# MoonlightHub.net
KiCad netlist of a schematic drawn in EAGLE
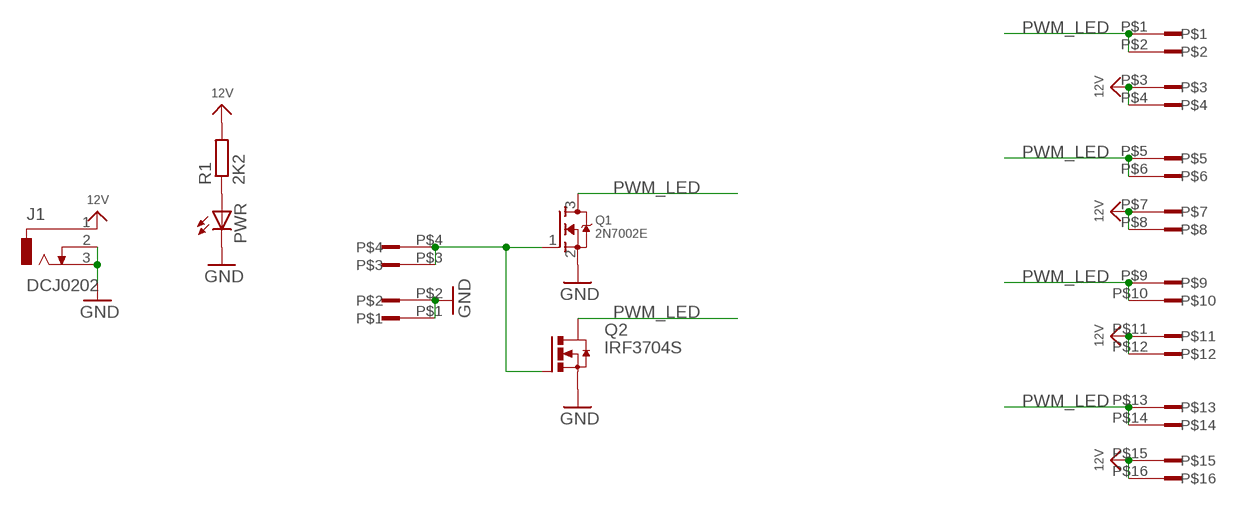
[diagram p0: schematic, sheet 1]

(export (version "E")
  (design (tool "Eeschema 10.0.6"))
  (components
    (comp (ref "CON1")
      (value "CONN2")
      (footprint "eagle-import:CONN2")
      (libsource (lib "eagle-import") (part "CONN2"))
    )
    (comp (ref "CON2")
      (value "CONN8")
      (footprint "eagle-import:CONN8")
      (libsource (lib "eagle-import") (part "CONN8"))
    )
    (comp (ref "J1")
      (value "DCJ0202")
      (footprint "eagle-import:DCJ0202")
      (libsource (lib "eagle-import") (part "DCJ0202"))
    )
    (comp (ref "PWR")
      (value "LED3MM")
      (footprint "eagle-import:LED3MM")
      (libsource (lib "eagle-import") (part "LED3MM"))
    )
    (comp (ref "Q1")
      (value "2N7002E")
      (footprint "eagle-import:SOT23-W")
      (libsource (lib "eagle-import") (part "MOSFET-NWAVE"))
    )
    (comp (ref "Q2")
      (value "IRF3704S")
      (footprint "eagle-import:D2PACK")
      (libsource (lib "eagle-import") (part "IRF3704S"))
    )
    (comp (ref "R1")
      (value "2K2")
      (footprint "eagle-import:R0805W")
      (libsource (lib "eagle-import") (part "R-EU_R0805W"))
    )
  )
  (nets
    (net (code "1") (name "/PWM_LED") (class "Default")
      (node (ref "CON2") (pin "P$1") (pinfunction "P$1_P$1") (pintype "bidirectional"))
      (node (ref "CON2") (pin "P$10") (pinfunction "P$10_P$10") (pintype "bidirectional"))
      (node (ref "CON2") (pin "P$13") (pinfunction "P$13_P$13") (pintype "bidirectional"))
      (node (ref "CON2") (pin "P$14") (pinfunction "P$14_P$14") (pintype "bidirectional"))
      (node (ref "CON2") (pin "P$2") (pinfunction "P$2_P$2") (pintype "bidirectional"))
      (node (ref "CON2") (pin "P$5") (pinfunction "P$5_P$5") (pintype "bidirectional"))
      (node (ref "CON2") (pin "P$6") (pinfunction "P$6_P$6") (pintype "bidirectional"))
      (node (ref "CON2") (pin "P$9") (pinfunction "P$9_P$9") (pintype "bidirectional"))
      (node (ref "Q1") (pin "3") (pinfunction "D_3") (pintype "bidirectional"))
      (node (ref "Q2") (pin "2") (pinfunction "D_2") (pintype "passive"))
    )
    (net (code "2") (name "12V") (class "Default")
      (node (ref "CON2") (pin "P$11") (pinfunction "P$11_P$11") (pintype "bidirectional"))
      (node (ref "CON2") (pin "P$12") (pinfunction "P$12_P$12") (pintype "bidirectional"))
      (node (ref "CON2") (pin "P$15") (pinfunction "P$15_P$15") (pintype "bidirectional"))
      (node (ref "CON2") (pin "P$16") (pinfunction "P$16_P$16") (pintype "bidirectional"))
      (node (ref "CON2") (pin "P$3") (pinfunction "P$3_P$3") (pintype "bidirectional"))
      (node (ref "CON2") (pin "P$4") (pinfunction "P$4_P$4") (pintype "bidirectional"))
      (node (ref "CON2") (pin "P$7") (pinfunction "P$7_P$7") (pintype "bidirectional"))
      (node (ref "CON2") (pin "P$8") (pinfunction "P$8_P$8") (pintype "bidirectional"))
      (node (ref "J1") (pin "1") (pinfunction "1_1") (pintype "passive"))
      (node (ref "R1") (pin "2") (pinfunction "2_2") (pintype "passive"))
    )
    (net (code "3") (name "GND") (class "Default")
      (node (ref "CON1") (pin "P$1") (pinfunction "P$1_P$1") (pintype "bidirectional"))
      (node (ref "CON1") (pin "P$2") (pinfunction "P$2_P$2") (pintype "bidirectional"))
      (node (ref "J1") (pin "2") (pinfunction "2_2") (pintype "passive"))
      (node (ref "J1") (pin "3") (pinfunction "3_3") (pintype "passive"))
      (node (ref "PWR") (pin "K") (pinfunction "C_K") (pintype "passive"))
      (node (ref "Q1") (pin "2") (pinfunction "S_2") (pintype "bidirectional"))
      (node (ref "Q2") (pin "3") (pinfunction "S_3") (pintype "passive"))
    )
    (net (code "4") (name "Net-(PWR-PadA)") (class "Default")
      (node (ref "PWR") (pin "A") (pinfunction "A_A") (pintype "passive"))
      (node (ref "R1") (pin "1") (pinfunction "1_1") (pintype "passive"))
    )
    (net (code "5") (name "Net-(Q1-G)") (class "Default")
      (node (ref "CON1") (pin "P$3") (pinfunction "P$3_P$3") (pintype "bidirectional"))
      (node (ref "CON1") (pin "P$4") (pinfunction "P$4_P$4") (pintype "bidirectional"))
      (node (ref "Q1") (pin "1") (pinfunction "G_1") (pintype "bidirectional"))
      (node (ref "Q2") (pin "1") (pinfunction "G_1") (pintype "passive"))
    )
  )
)
